# ACEstat_carrier.net
KiCad netlist of a schematic drawn in Altium Designer
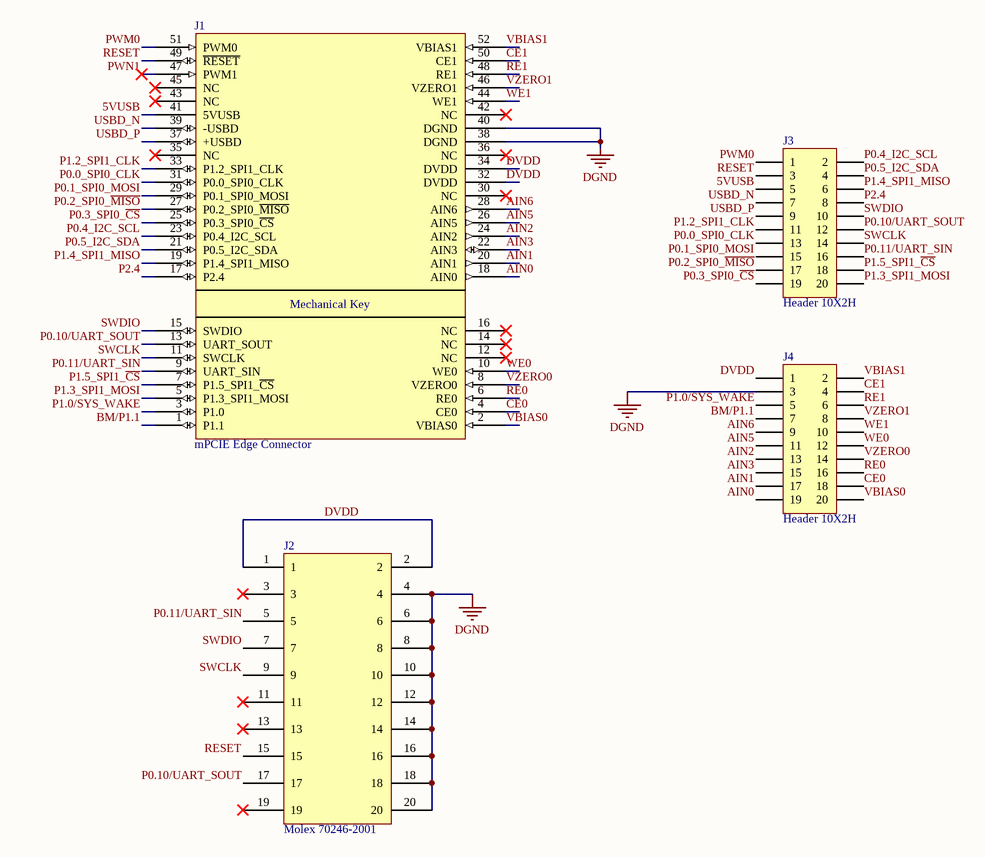
[diagram p0: ACEstat_carrier.SchDoc]

(export (version "E")
  (design (tool "Eeschema 10.0.6"))
  (components
    (comp (ref "J1")
      (value "mPCIE Edge Connector")
      (footprint "MPCIE_BOARD_CONNECTOR")
      (libsource (lib "ACEstat") (part "mPCIE_Edge"))
    )
    (comp (ref "J2")
      (value "Molex 70246-2001")
      (footprint "Molex 70246-2001")
      (description "20-pin JTAG female connector")
      (libsource (lib "ACEstat") (part "Molex 70246-2001"))
    )
    (comp (ref "J3")
      (value "Header 10X2H")
      (footprint "HDR2X10H")
      (description "Header, 10-Pin, Dual row, Right Angle")
      (fields (field (name "PUBLISHER") "Altium Limited"))
      (libsource (lib "Miscellaneous Connectors") (part "Header 10X2H"))
    )
    (comp (ref "J4")
      (value "Header 10X2H")
      (footprint "HDR2X10H")
      (description "Header, 10-Pin, Dual row, Right Angle")
      (fields (field (name "PUBLISHER") "Altium Limited"))
      (libsource (lib "Miscellaneous Connectors") (part "Header 10X2H"))
    )
  )
  (nets
    (net (code "1") (name "/5VUSB") (class "Default")
      (node (ref "J1") (pin "41") (pinfunction "5VUSB_41") (pintype "power_in"))
      (node (ref "J3") (pin "5") (pinfunction "5_5") (pintype "passive"))
    )
    (net (code "2") (name "/AIN0") (class "Default")
      (node (ref "J1") (pin "18") (pinfunction "AIN0_18") (pintype "output"))
      (node (ref "J4") (pin "19") (pinfunction "19_19") (pintype "passive"))
    )
    (net (code "3") (name "/AIN1") (class "Default")
      (node (ref "J1") (pin "20") (pinfunction "AIN1_20") (pintype "output"))
      (node (ref "J4") (pin "17") (pinfunction "17_17") (pintype "passive"))
    )
    (net (code "4") (name "/AIN2") (class "Default")
      (node (ref "J1") (pin "24") (pinfunction "AIN2_24") (pintype "output"))
      (node (ref "J4") (pin "13") (pinfunction "13_13") (pintype "passive"))
    )
    (net (code "5") (name "/AIN3") (class "Default")
      (node (ref "J1") (pin "22") (pinfunction "AIN3_22") (pintype "bidirectional"))
      (node (ref "J4") (pin "15") (pinfunction "15_15") (pintype "passive"))
    )
    (net (code "6") (name "/AIN5") (class "Default")
      (node (ref "J1") (pin "26") (pinfunction "AIN5_26") (pintype "output"))
      (node (ref "J4") (pin "11") (pinfunction "11_11") (pintype "passive"))
    )
    (net (code "7") (name "/AIN6") (class "Default")
      (node (ref "J1") (pin "28") (pinfunction "AIN6_28") (pintype "output"))
      (node (ref "J4") (pin "9") (pinfunction "9_9") (pintype "passive"))
    )
    (net (code "8") (name "/BM{slash}P1.1") (class "Default")
      (node (ref "J1") (pin "1") (pinfunction "P1.1_1") (pintype "bidirectional"))
      (node (ref "J4") (pin "7") (pinfunction "7_7") (pintype "passive"))
    )
    (net (code "9") (name "/CE0") (class "Default")
      (node (ref "J1") (pin "4") (pinfunction "CE0_4") (pintype "input"))
      (node (ref "J4") (pin "18") (pinfunction "18_18") (pintype "passive"))
    )
    (net (code "10") (name "/CE1") (class "Default")
      (node (ref "J1") (pin "50") (pinfunction "CE1_50") (pintype "input"))
      (node (ref "J4") (pin "4") (pinfunction "4_4") (pintype "passive"))
    )
    (net (code "11") (name "/DVDD") (class "Default")
      (node (ref "J1") (pin "32") (pinfunction "DVDD_32") (pintype "power_in"))
      (node (ref "J1") (pin "34") (pinfunction "DVDD_34") (pintype "power_in"))
      (node (ref "J2") (pin "1") (pinfunction "1_1") (pintype "passive"))
      (node (ref "J2") (pin "2") (pinfunction "2_2") (pintype "passive"))
      (node (ref "J4") (pin "1") (pinfunction "1_1") (pintype "passive"))
    )
    (net (code "12") (name "/P0.0_SPI0_CLK") (class "Default")
      (node (ref "J1") (pin "31") (pinfunction "P0.0_SPI0_CLK_31") (pintype "bidirectional"))
      (node (ref "J3") (pin "13") (pinfunction "13_13") (pintype "passive"))
    )
    (net (code "13") (name "/P0.1_SPI0_MOSI") (class "Default")
      (node (ref "J1") (pin "29") (pinfunction "P0.1_SPI0_MOSI_29") (pintype "bidirectional"))
      (node (ref "J3") (pin "15") (pinfunction "15_15") (pintype "passive"))
    )
    (net (code "14") (name "/P0.2_SPI0_~{MISO}") (class "Default")
      (node (ref "J1") (pin "27") (pinfunction "P0.2_SPI0_~{MISO}_27") (pintype "bidirectional"))
      (node (ref "J3") (pin "17") (pinfunction "17_17") (pintype "passive"))
    )
    (net (code "15") (name "/P0.3_SPI0_~{CS}") (class "Default")
      (node (ref "J1") (pin "25") (pinfunction "P0.3_SPI0_~{CS}_25") (pintype "bidirectional"))
      (node (ref "J3") (pin "19") (pinfunction "19_19") (pintype "passive"))
    )
    (net (code "16") (name "/P0.4_I2C_SCL") (class "Default")
      (node (ref "J1") (pin "23") (pinfunction "P0.4_I2C_SCL_23") (pintype "bidirectional"))
      (node (ref "J3") (pin "2") (pinfunction "2_2") (pintype "passive"))
    )
    (net (code "17") (name "/P0.5_I2C_SDA") (class "Default")
      (node (ref "J1") (pin "21") (pinfunction "P0.5_I2C_SDA_21") (pintype "bidirectional"))
      (node (ref "J3") (pin "4") (pinfunction "4_4") (pintype "passive"))
    )
    (net (code "18") (name "/P0.10{slash}UART_SOUT") (class "Default")
      (node (ref "J1") (pin "13") (pinfunction "UART_SOUT_13") (pintype "bidirectional"))
      (node (ref "J2") (pin "17") (pinfunction "17_17") (pintype "passive"))
      (node (ref "J3") (pin "12") (pinfunction "12_12") (pintype "passive"))
    )
    (net (code "19") (name "/P0.11{slash}UART_SIN") (class "Default")
      (node (ref "J1") (pin "9") (pinfunction "UART_SIN_9") (pintype "bidirectional"))
      (node (ref "J2") (pin "5") (pinfunction "5_5") (pintype "passive"))
      (node (ref "J3") (pin "16") (pinfunction "16_16") (pintype "passive"))
    )
    (net (code "20") (name "/P1.0{slash}SYS_WAKE") (class "Default")
      (node (ref "J1") (pin "3") (pinfunction "P1.0_3") (pintype "bidirectional"))
      (node (ref "J4") (pin "5") (pinfunction "5_5") (pintype "passive"))
    )
    (net (code "21") (name "/P1.2_SPI1_CLK") (class "Default")
      (node (ref "J1") (pin "33") (pinfunction "P1.2_SPI1_CLK_33") (pintype "bidirectional"))
      (node (ref "J3") (pin "11") (pinfunction "11_11") (pintype "passive"))
    )
    (net (code "22") (name "/P1.3_SPI1_MOSI") (class "Default")
      (node (ref "J1") (pin "5") (pinfunction "P1.3_SPI1_MOSI_5") (pintype "bidirectional"))
      (node (ref "J3") (pin "20") (pinfunction "20_20") (pintype "passive"))
    )
    (net (code "23") (name "/P1.4_SPI1_MISO") (class "Default")
      (node (ref "J1") (pin "19") (pinfunction "P1.4_SPI1_MISO_19") (pintype "bidirectional"))
      (node (ref "J3") (pin "6") (pinfunction "6_6") (pintype "passive"))
    )
    (net (code "24") (name "/P1.5_SPI1_~{CS}") (class "Default")
      (node (ref "J1") (pin "7") (pinfunction "P1.5_SPI1_~{CS}_7") (pintype "bidirectional"))
      (node (ref "J3") (pin "18") (pinfunction "18_18") (pintype "passive"))
    )
    (net (code "25") (name "/P2.4") (class "Default")
      (node (ref "J1") (pin "17") (pinfunction "P2.4_17") (pintype "bidirectional"))
      (node (ref "J3") (pin "8") (pinfunction "8_8") (pintype "passive"))
    )
    (net (code "26") (name "/PWM0") (class "Default")
      (node (ref "J1") (pin "51") (pinfunction "PWM0_51") (pintype "input"))
      (node (ref "J3") (pin "1") (pinfunction "1_1") (pintype "passive"))
    )
    (net (code "27") (name "/PWN1") (class "Default")
      (node (ref "J1") (pin "47") (pinfunction "PWM1_47") (pintype "input+no_connect"))
    )
    (net (code "28") (name "/RE0") (class "Default")
      (node (ref "J1") (pin "6") (pinfunction "RE0_6") (pintype "input"))
      (node (ref "J4") (pin "16") (pinfunction "16_16") (pintype "passive"))
    )
    (net (code "29") (name "/RE1") (class "Default")
      (node (ref "J1") (pin "48") (pinfunction "RE1_48") (pintype "input"))
      (node (ref "J4") (pin "6") (pinfunction "6_6") (pintype "passive"))
    )
    (net (code "30") (name "/RESET") (class "Default")
      (node (ref "J1") (pin "49") (pinfunction "~{RESET}_49") (pintype "bidirectional"))
      (node (ref "J2") (pin "15") (pinfunction "15_15") (pintype "passive"))
      (node (ref "J3") (pin "3") (pinfunction "3_3") (pintype "passive"))
    )
    (net (code "31") (name "/SWCLK") (class "Default")
      (node (ref "J1") (pin "11") (pinfunction "SWCLK_11") (pintype "bidirectional"))
      (node (ref "J2") (pin "9") (pinfunction "9_9") (pintype "passive"))
      (node (ref "J3") (pin "14") (pinfunction "14_14") (pintype "passive"))
    )
    (net (code "32") (name "/SWDIO") (class "Default")
      (node (ref "J1") (pin "15") (pinfunction "SWDIO_15") (pintype "bidirectional"))
      (node (ref "J2") (pin "7") (pinfunction "7_7") (pintype "passive"))
      (node (ref "J3") (pin "10") (pinfunction "10_10") (pintype "passive"))
    )
    (net (code "33") (name "/USBD_N") (class "Default")
      (node (ref "J1") (pin "39") (pinfunction "-USBD_39") (pintype "bidirectional"))
      (node (ref "J3") (pin "7") (pinfunction "7_7") (pintype "passive"))
    )
    (net (code "34") (name "/USBD_P") (class "Default")
      (node (ref "J1") (pin "37") (pinfunction "+USBD_37") (pintype "bidirectional"))
      (node (ref "J3") (pin "9") (pinfunction "9_9") (pintype "passive"))
    )
    (net (code "35") (name "/VBIAS0") (class "Default")
      (node (ref "J1") (pin "2") (pinfunction "VBIAS0_2") (pintype "input"))
      (node (ref "J4") (pin "20") (pinfunction "20_20") (pintype "passive"))
    )
    (net (code "36") (name "/VBIAS1") (class "Default")
      (node (ref "J1") (pin "52") (pinfunction "VBIAS1_52") (pintype "input"))
      (node (ref "J4") (pin "2") (pinfunction "2_2") (pintype "passive"))
    )
    (net (code "37") (name "/VZERO0") (class "Default")
      (node (ref "J1") (pin "8") (pinfunction "VZERO0_8") (pintype "input"))
      (node (ref "J4") (pin "14") (pinfunction "14_14") (pintype "passive"))
    )
    (net (code "38") (name "/VZERO1") (class "Default")
      (node (ref "J1") (pin "46") (pinfunction "VZERO1_46") (pintype "input"))
      (node (ref "J4") (pin "8") (pinfunction "8_8") (pintype "passive"))
    )
    (net (code "39") (name "/WE0") (class "Default")
      (node (ref "J1") (pin "10") (pinfunction "WE0_10") (pintype "input"))
      (node (ref "J4") (pin "12") (pinfunction "12_12") (pintype "passive"))
    )
    (net (code "40") (name "/WE1") (class "Default")
      (node (ref "J1") (pin "44") (pinfunction "WE1_44") (pintype "input"))
      (node (ref "J4") (pin "10") (pinfunction "10_10") (pintype "passive"))
    )
    (net (code "41") (name "DGND") (class "Default")
      (node (ref "J1") (pin "38") (pinfunction "DGND_38") (pintype "power_in"))
      (node (ref "J1") (pin "40") (pinfunction "DGND_40") (pintype "power_in"))
      (node (ref "J2") (pin "10") (pinfunction "10_10") (pintype "passive"))
      (node (ref "J2") (pin "12") (pinfunction "12_12") (pintype "passive"))
      (node (ref "J2") (pin "14") (pinfunction "14_14") (pintype "passive"))
      (node (ref "J2") (pin "16") (pinfunction "16_16") (pintype "passive"))
      (node (ref "J2") (pin "18") (pinfunction "18_18") (pintype "passive"))
      (node (ref "J2") (pin "20") (pinfunction "20_20") (pintype "passive"))
      (node (ref "J2") (pin "4") (pinfunction "4_4") (pintype "passive"))
      (node (ref "J2") (pin "6") (pinfunction "6_6") (pintype "passive"))
      (node (ref "J2") (pin "8") (pinfunction "8_8") (pintype "passive"))
      (node (ref "J4") (pin "3") (pinfunction "3_3") (pintype "passive"))
    )
    (net (code "42") (name "unconnected-(J1-NC-Pad12)") (class "Default")
      (node (ref "J1") (pin "12") (pinfunction "NC_12") (pintype "passive+no_connect"))
    )
    (net (code "43") (name "unconnected-(J1-NC-Pad14)") (class "Default")
      (node (ref "J1") (pin "14") (pinfunction "NC_14") (pintype "passive+no_connect"))
    )
    (net (code "44") (name "unconnected-(J1-NC-Pad16)") (class "Default")
      (node (ref "J1") (pin "16") (pinfunction "NC_16") (pintype "passive+no_connect"))
    )
    (net (code "45") (name "unconnected-(J1-NC-Pad30)") (class "Default")
      (node (ref "J1") (pin "30") (pinfunction "NC_30") (pintype "passive+no_connect"))
    )
    (net (code "46") (name "unconnected-(J1-NC-Pad35)") (class "Default")
      (node (ref "J1") (pin "35") (pinfunction "NC_35") (pintype "passive+no_connect"))
    )
    (net (code "47") (name "unconnected-(J1-NC-Pad36)") (class "Default")
      (node (ref "J1") (pin "36") (pinfunction "NC_36") (pintype "passive+no_connect"))
    )
    (net (code "48") (name "unconnected-(J1-NC-Pad42)") (class "Default")
      (node (ref "J1") (pin "42") (pinfunction "NC_42") (pintype "passive+no_connect"))
    )
    (net (code "49") (name "unconnected-(J1-NC-Pad43)") (class "Default")
      (node (ref "J1") (pin "43") (pinfunction "NC_43") (pintype "passive+no_connect"))
    )
    (net (code "50") (name "unconnected-(J1-NC-Pad45)") (class "Default")
      (node (ref "J1") (pin "45") (pinfunction "NC_45") (pintype "passive+no_connect"))
    )
    (net (code "51") (name "unconnected-(J2-Pad3)") (class "Default")
      (node (ref "J2") (pin "3") (pinfunction "3_3") (pintype "passive+no_connect"))
    )
    (net (code "52") (name "unconnected-(J2-Pad11)") (class "Default")
      (node (ref "J2") (pin "11") (pinfunction "11_11") (pintype "passive+no_connect"))
    )
    (net (code "53") (name "unconnected-(J2-Pad13)") (class "Default")
      (node (ref "J2") (pin "13") (pinfunction "13_13") (pintype "passive+no_connect"))
    )
    (net (code "54") (name "unconnected-(J2-Pad19)") (class "Default")
      (node (ref "J2") (pin "19") (pinfunction "19_19") (pintype "passive+no_connect"))
    )
  )
)
